# zedAF.net
KiCad netlist of a schematic drawn in EAGLE
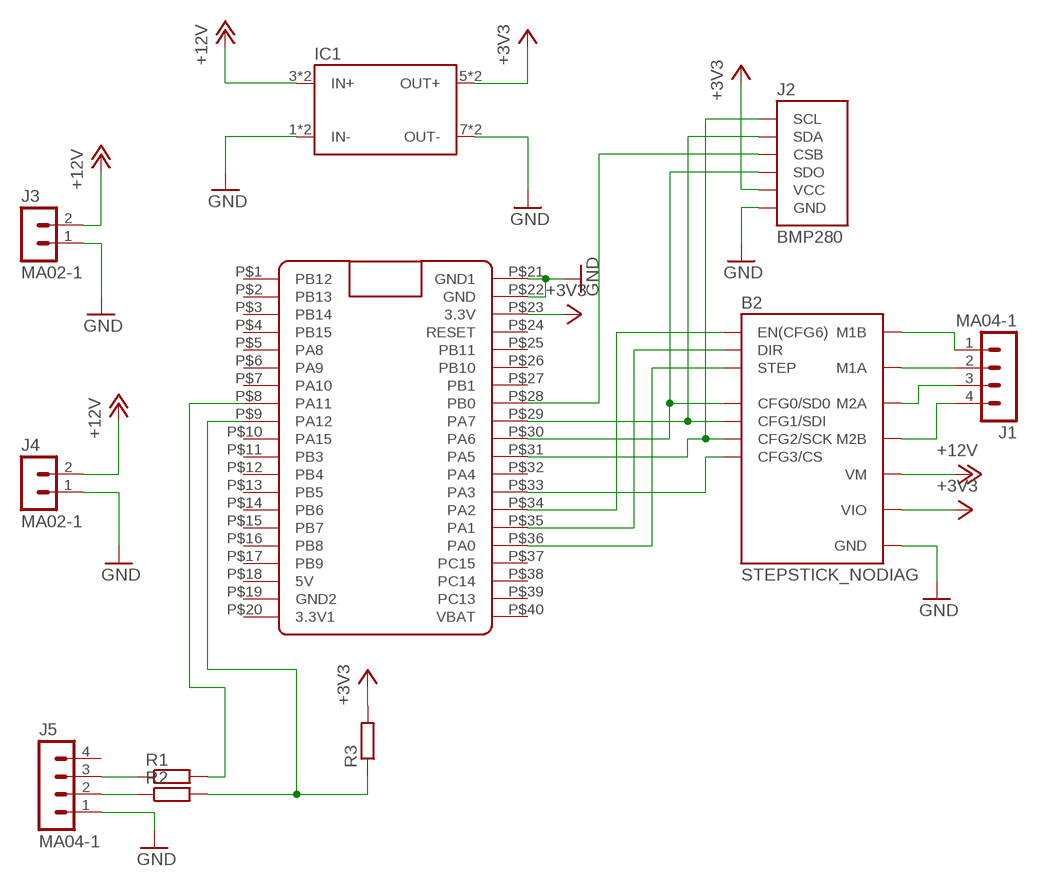
[diagram p0: schematic, sheet 1]

(export (version "E")
  (design (tool "Eeschema 10.0.6"))
  (components
    (comp (ref "B2")
      (value "STEPSTICK_NODIAG")
      (footprint "eagle-import:STEPSTICK")
      (libsource (lib "eagle-import") (part "STEPSTICK_NODIAG"))
    )
    (comp (ref "IC1")
      (value "DC/DCDC")
      (footprint "eagle-import:DC_DC")
      (libsource (lib "eagle-import") (part "DC/DCDC"))
    )
    (comp (ref "J1")
      (value "MA04-1")
      (footprint "eagle-import:MA04-1")
      (libsource (lib "eagle-import") (part "MA04-1"))
    )
    (comp (ref "J2")
      (value "BMP280")
      (footprint "eagle-import:BMP280-1X6")
      (libsource (lib "eagle-import") (part "BMP280"))
    )
    (comp (ref "J3")
      (value "MA02-1")
      (footprint "eagle-import:MA02-1")
      (libsource (lib "eagle-import") (part "MA02-1"))
    )
    (comp (ref "J4")
      (value "MA02-1")
      (footprint "eagle-import:MA02-1")
      (libsource (lib "eagle-import") (part "MA02-1"))
    )
    (comp (ref "J5")
      (value "MA04-1")
      (footprint "eagle-import:MA04-1")
      (libsource (lib "eagle-import") (part "MA04-1"))
    )
    (comp (ref "R1")
      (value "R-EU_R1206")
      (footprint "eagle-import:R1206")
      (libsource (lib "eagle-import") (part "R-EU_R1206"))
    )
    (comp (ref "R2")
      (value "R-EU_R1206")
      (footprint "eagle-import:R1206")
      (libsource (lib "eagle-import") (part "R-EU_R1206"))
    )
    (comp (ref "R3")
      (value "R-EU_R1206")
      (footprint "eagle-import:R1206")
      (libsource (lib "eagle-import") (part "R-EU_R1206"))
    )
    (comp (ref "U$1")
      (value "BLUE_PILLWIDE")
      (footprint "eagle-import:BLUE_PILL_WIDE")
      (libsource (lib "eagle-import") (part "BLUE_PILLWIDE"))
    )
  )
  (nets
    (net (code "1") (name "+3V3") (class "Default")
      (node (ref "B2") (pin "VIO") (pinfunction "VIO_VIO") (pintype "power_in"))
      (node (ref "IC1") (pin "5") (pinfunction "OUT+_5") (pintype "power_in"))
      (node (ref "IC1") (pin "6") (pinfunction "OUT+_6") (pintype "power_in"))
      (node (ref "J2") (pin "1") (pinfunction "VCC_1") (pintype "power_in"))
      (node (ref "R3") (pin "2") (pinfunction "2_2") (pintype "passive"))
      (node (ref "U$1") (pin "P$23") (pinfunction "3.3V_P$23") (pintype "bidirectional"))
    )
    (net (code "2") (name "+12V") (class "Default")
      (node (ref "B2") (pin "VM") (pinfunction "VM_VM") (pintype "power_in"))
      (node (ref "IC1") (pin "3") (pinfunction "IN+_3") (pintype "power_in"))
      (node (ref "IC1") (pin "4") (pinfunction "IN+_4") (pintype "power_in"))
      (node (ref "J3") (pin "2") (pinfunction "2_2") (pintype "passive"))
      (node (ref "J4") (pin "2") (pinfunction "2_2") (pintype "passive"))
    )
    (net (code "3") (name "GND") (class "Default")
      (node (ref "B2") (pin "GND@1") (pinfunction "GND_GND@1") (pintype "power_in"))
      (node (ref "B2") (pin "GND@2") (pinfunction "GND_GND@2") (pintype "power_in"))
      (node (ref "IC1") (pin "1") (pinfunction "IN-_1") (pintype "power_in"))
      (node (ref "IC1") (pin "2") (pinfunction "IN-_2") (pintype "power_in"))
      (node (ref "IC1") (pin "7") (pinfunction "OUT-_7") (pintype "power_in"))
      (node (ref "IC1") (pin "8") (pinfunction "OUT-_8") (pintype "power_in"))
      (node (ref "J2") (pin "2") (pinfunction "GND_2") (pintype "power_in"))
      (node (ref "J3") (pin "1") (pinfunction "1_1") (pintype "passive"))
      (node (ref "J4") (pin "1") (pinfunction "1_1") (pintype "passive"))
      (node (ref "J5") (pin "1") (pinfunction "1_1") (pintype "passive"))
      (node (ref "U$1") (pin "P$21") (pinfunction "GND1_P$21") (pintype "power_in"))
      (node (ref "U$1") (pin "P$22") (pinfunction "GND_P$22") (pintype "bidirectional"))
    )
    (net (code "4") (name "Net-(B2-CFG0{slash}SD0)") (class "Default")
      (node (ref "B2") (pin "NC/CFG0") (pinfunction "CFG0/SD0_NC/CFG0") (pintype "bidirectional"))
      (node (ref "J2") (pin "6") (pinfunction "SDO_6") (pintype "bidirectional"))
      (node (ref "U$1") (pin "P$30") (pinfunction "PA6_P$30") (pintype "bidirectional"))
    )
    (net (code "5") (name "Net-(B2-CFG1{slash}SDI)") (class "Default")
      (node (ref "B2") (pin "CFG1") (pinfunction "CFG1/SDI_CFG1") (pintype "bidirectional"))
      (node (ref "J2") (pin "4") (pinfunction "SDA_4") (pintype "bidirectional"))
      (node (ref "U$1") (pin "P$29") (pinfunction "PA7_P$29") (pintype "bidirectional"))
    )
    (net (code "6") (name "Net-(B2-CFG2{slash}SCK)") (class "Default")
      (node (ref "B2") (pin "CFG2") (pinfunction "CFG2/SCK_CFG2") (pintype "bidirectional"))
      (node (ref "J2") (pin "3") (pinfunction "SCL_3") (pintype "bidirectional"))
      (node (ref "U$1") (pin "P$31") (pinfunction "PA5_P$31") (pintype "bidirectional"))
    )
    (net (code "7") (name "Net-(B2-CFG3{slash}CS)") (class "Default")
      (node (ref "B2") (pin "CFG3") (pinfunction "CFG3/CS_CFG3") (pintype "bidirectional"))
      (node (ref "U$1") (pin "P$33") (pinfunction "PA3_P$33") (pintype "bidirectional"))
    )
    (net (code "8") (name "Net-(B2-EN(CFG6))") (class "Default")
      (node (ref "B2") (pin "EN") (pinfunction "EN(CFG6)_EN") (pintype "bidirectional"))
      (node (ref "U$1") (pin "P$34") (pinfunction "PA2_P$34") (pintype "bidirectional"))
    )
    (net (code "9") (name "Net-(B2-PadM1A)") (class "Default")
      (node (ref "B2") (pin "M1A") (pinfunction "M1A_M1A") (pintype "output"))
      (node (ref "J1") (pin "2") (pinfunction "2_2") (pintype "passive"))
    )
    (net (code "10") (name "Net-(B2-PadM1B)") (class "Default")
      (node (ref "B2") (pin "M1B") (pinfunction "M1B_M1B") (pintype "output"))
      (node (ref "J1") (pin "1") (pinfunction "1_1") (pintype "passive"))
    )
    (net (code "11") (name "Net-(B2-PadM2A)") (class "Default")
      (node (ref "B2") (pin "M2A") (pinfunction "M2A_M2A") (pintype "output"))
      (node (ref "J1") (pin "3") (pinfunction "3_3") (pintype "passive"))
    )
    (net (code "12") (name "Net-(B2-PadM2B)") (class "Default")
      (node (ref "B2") (pin "M2B") (pinfunction "M2B_M2B") (pintype "output"))
      (node (ref "J1") (pin "4") (pinfunction "4_4") (pintype "passive"))
    )
    (net (code "13") (name "Net-(J2-CSB)") (class "Default")
      (node (ref "J2") (pin "5") (pinfunction "CSB_5") (pintype "bidirectional"))
      (node (ref "U$1") (pin "P$28") (pinfunction "PB0_P$28") (pintype "bidirectional"))
    )
    (net (code "14") (name "Net-(J5-Pad2)") (class "Default")
      (node (ref "J5") (pin "2") (pinfunction "2_2") (pintype "passive"))
      (node (ref "R2") (pin "1") (pinfunction "1_1") (pintype "passive"))
    )
    (net (code "15") (name "Net-(J5-Pad3)") (class "Default")
      (node (ref "J5") (pin "3") (pinfunction "3_3") (pintype "passive"))
      (node (ref "R1") (pin "1") (pinfunction "1_1") (pintype "passive"))
    )
    (net (code "16") (name "Net-(U$1-PA0)") (class "Default")
      (node (ref "B2") (pin "STEP") (pinfunction "STEP_STEP") (pintype "bidirectional"))
      (node (ref "U$1") (pin "P$36") (pinfunction "PA0_P$36") (pintype "bidirectional"))
    )
    (net (code "17") (name "Net-(U$1-PA1)") (class "Default")
      (node (ref "B2") (pin "DIR") (pinfunction "DIR_DIR") (pintype "bidirectional"))
      (node (ref "U$1") (pin "P$35") (pinfunction "PA1_P$35") (pintype "bidirectional"))
    )
    (net (code "18") (name "Net-(U$1-PA11)") (class "Default")
      (node (ref "R1") (pin "2") (pinfunction "2_2") (pintype "passive"))
      (node (ref "U$1") (pin "P$8") (pinfunction "PA11_P$8") (pintype "bidirectional"))
    )
    (net (code "19") (name "Net-(U$1-PA12)") (class "Default")
      (node (ref "R2") (pin "2") (pinfunction "2_2") (pintype "passive"))
      (node (ref "R3") (pin "1") (pinfunction "1_1") (pintype "passive"))
      (node (ref "U$1") (pin "P$9") (pinfunction "PA12_P$9") (pintype "bidirectional"))
    )
    (net (code "20") (name "unconnected-(J5-Pad4)") (class "Default")
      (node (ref "J5") (pin "4") (pinfunction "4_4") (pintype "passive"))
    )
    (net (code "21") (name "unconnected-(U$1-3.3V1-PadP$20)") (class "Default")
      (node (ref "U$1") (pin "P$20") (pinfunction "3.3V1_P$20") (pintype "bidirectional"))
    )
    (net (code "22") (name "unconnected-(U$1-5V-PadP$18)") (class "Default")
      (node (ref "U$1") (pin "P$18") (pinfunction "5V_P$18") (pintype "bidirectional"))
    )
    (net (code "23") (name "unconnected-(U$1-GND2-PadP$19)") (class "Default")
      (node (ref "U$1") (pin "P$19") (pinfunction "GND2_P$19") (pintype "bidirectional"))
    )
    (net (code "24") (name "unconnected-(U$1-PA4-PadP$32)") (class "Default")
      (node (ref "U$1") (pin "P$32") (pinfunction "PA4_P$32") (pintype "bidirectional"))
    )
    (net (code "25") (name "unconnected-(U$1-PA8-PadP$5)") (class "Default")
      (node (ref "U$1") (pin "P$5") (pinfunction "PA8_P$5") (pintype "bidirectional"))
    )
    (net (code "26") (name "unconnected-(U$1-PA9-PadP$6)") (class "Default")
      (node (ref "U$1") (pin "P$6") (pinfunction "PA9_P$6") (pintype "bidirectional"))
    )
    (net (code "27") (name "unconnected-(U$1-PA10-PadP$7)") (class "Default")
      (node (ref "U$1") (pin "P$7") (pinfunction "PA10_P$7") (pintype "bidirectional"))
    )
    (net (code "28") (name "unconnected-(U$1-PA15-PadP$10)") (class "Default")
      (node (ref "U$1") (pin "P$10") (pinfunction "PA15_P$10") (pintype "bidirectional"))
    )
    (net (code "29") (name "unconnected-(U$1-PB1-PadP$27)") (class "Default")
      (node (ref "U$1") (pin "P$27") (pinfunction "PB1_P$27") (pintype "bidirectional"))
    )
    (net (code "30") (name "unconnected-(U$1-PB3-PadP$11)") (class "Default")
      (node (ref "U$1") (pin "P$11") (pinfunction "PB3_P$11") (pintype "bidirectional"))
    )
    (net (code "31") (name "unconnected-(U$1-PB4-PadP$12)") (class "Default")
      (node (ref "U$1") (pin "P$12") (pinfunction "PB4_P$12") (pintype "bidirectional"))
    )
    (net (code "32") (name "unconnected-(U$1-PB5-PadP$13)") (class "Default")
      (node (ref "U$1") (pin "P$13") (pinfunction "PB5_P$13") (pintype "bidirectional"))
    )
    (net (code "33") (name "unconnected-(U$1-PB6-PadP$14)") (class "Default")
      (node (ref "U$1") (pin "P$14") (pinfunction "PB6_P$14") (pintype "bidirectional"))
    )
    (net (code "34") (name "unconnected-(U$1-PB7-PadP$15)") (class "Default")
      (node (ref "U$1") (pin "P$15") (pinfunction "PB7_P$15") (pintype "bidirectional"))
    )
    (net (code "35") (name "unconnected-(U$1-PB8-PadP$16)") (class "Default")
      (node (ref "U$1") (pin "P$16") (pinfunction "PB8_P$16") (pintype "bidirectional"))
    )
    (net (code "36") (name "unconnected-(U$1-PB9-PadP$17)") (class "Default")
      (node (ref "U$1") (pin "P$17") (pinfunction "PB9_P$17") (pintype "bidirectional"))
    )
    (net (code "37") (name "unconnected-(U$1-PB10-PadP$26)") (class "Default")
      (node (ref "U$1") (pin "P$26") (pinfunction "PB10_P$26") (pintype "bidirectional"))
    )
    (net (code "38") (name "unconnected-(U$1-PB11-PadP$25)") (class "Default")
      (node (ref "U$1") (pin "P$25") (pinfunction "PB11_P$25") (pintype "bidirectional"))
    )
    (net (code "39") (name "unconnected-(U$1-PB12-PadP$1)") (class "Default")
      (node (ref "U$1") (pin "P$1") (pinfunction "PB12_P$1") (pintype "bidirectional"))
    )
    (net (code "40") (name "unconnected-(U$1-PB13-PadP$2)") (class "Default")
      (node (ref "U$1") (pin "P$2") (pinfunction "PB13_P$2") (pintype "bidirectional"))
    )
    (net (code "41") (name "unconnected-(U$1-PB14-PadP$3)") (class "Default")
      (node (ref "U$1") (pin "P$3") (pinfunction "PB14_P$3") (pintype "bidirectional"))
    )
    (net (code "42") (name "unconnected-(U$1-PB15-PadP$4)") (class "Default")
      (node (ref "U$1") (pin "P$4") (pinfunction "PB15_P$4") (pintype "bidirectional"))
    )
    (net (code "43") (name "unconnected-(U$1-PC13-PadP$39)") (class "Default")
      (node (ref "U$1") (pin "P$39") (pinfunction "PC13_P$39") (pintype "bidirectional"))
    )
    (net (code "44") (name "unconnected-(U$1-PC14-PadP$38)") (class "Default")
      (node (ref "U$1") (pin "P$38") (pinfunction "PC14_P$38") (pintype "bidirectional"))
    )
    (net (code "45") (name "unconnected-(U$1-PC15-PadP$37)") (class "Default")
      (node (ref "U$1") (pin "P$37") (pinfunction "PC15_P$37") (pintype "bidirectional"))
    )
    (net (code "46") (name "unconnected-(U$1-RESET-PadP$24)") (class "Default")
      (node (ref "U$1") (pin "P$24") (pinfunction "RESET_P$24") (pintype "bidirectional"))
    )
    (net (code "47") (name "unconnected-(U$1-VBAT-PadP$40)") (class "Default")
      (node (ref "U$1") (pin "P$40") (pinfunction "VBAT_P$40") (pintype "bidirectional"))
    )
  )
)
